# module.net
KiCad netlist of a schematic drawn in EAGLE
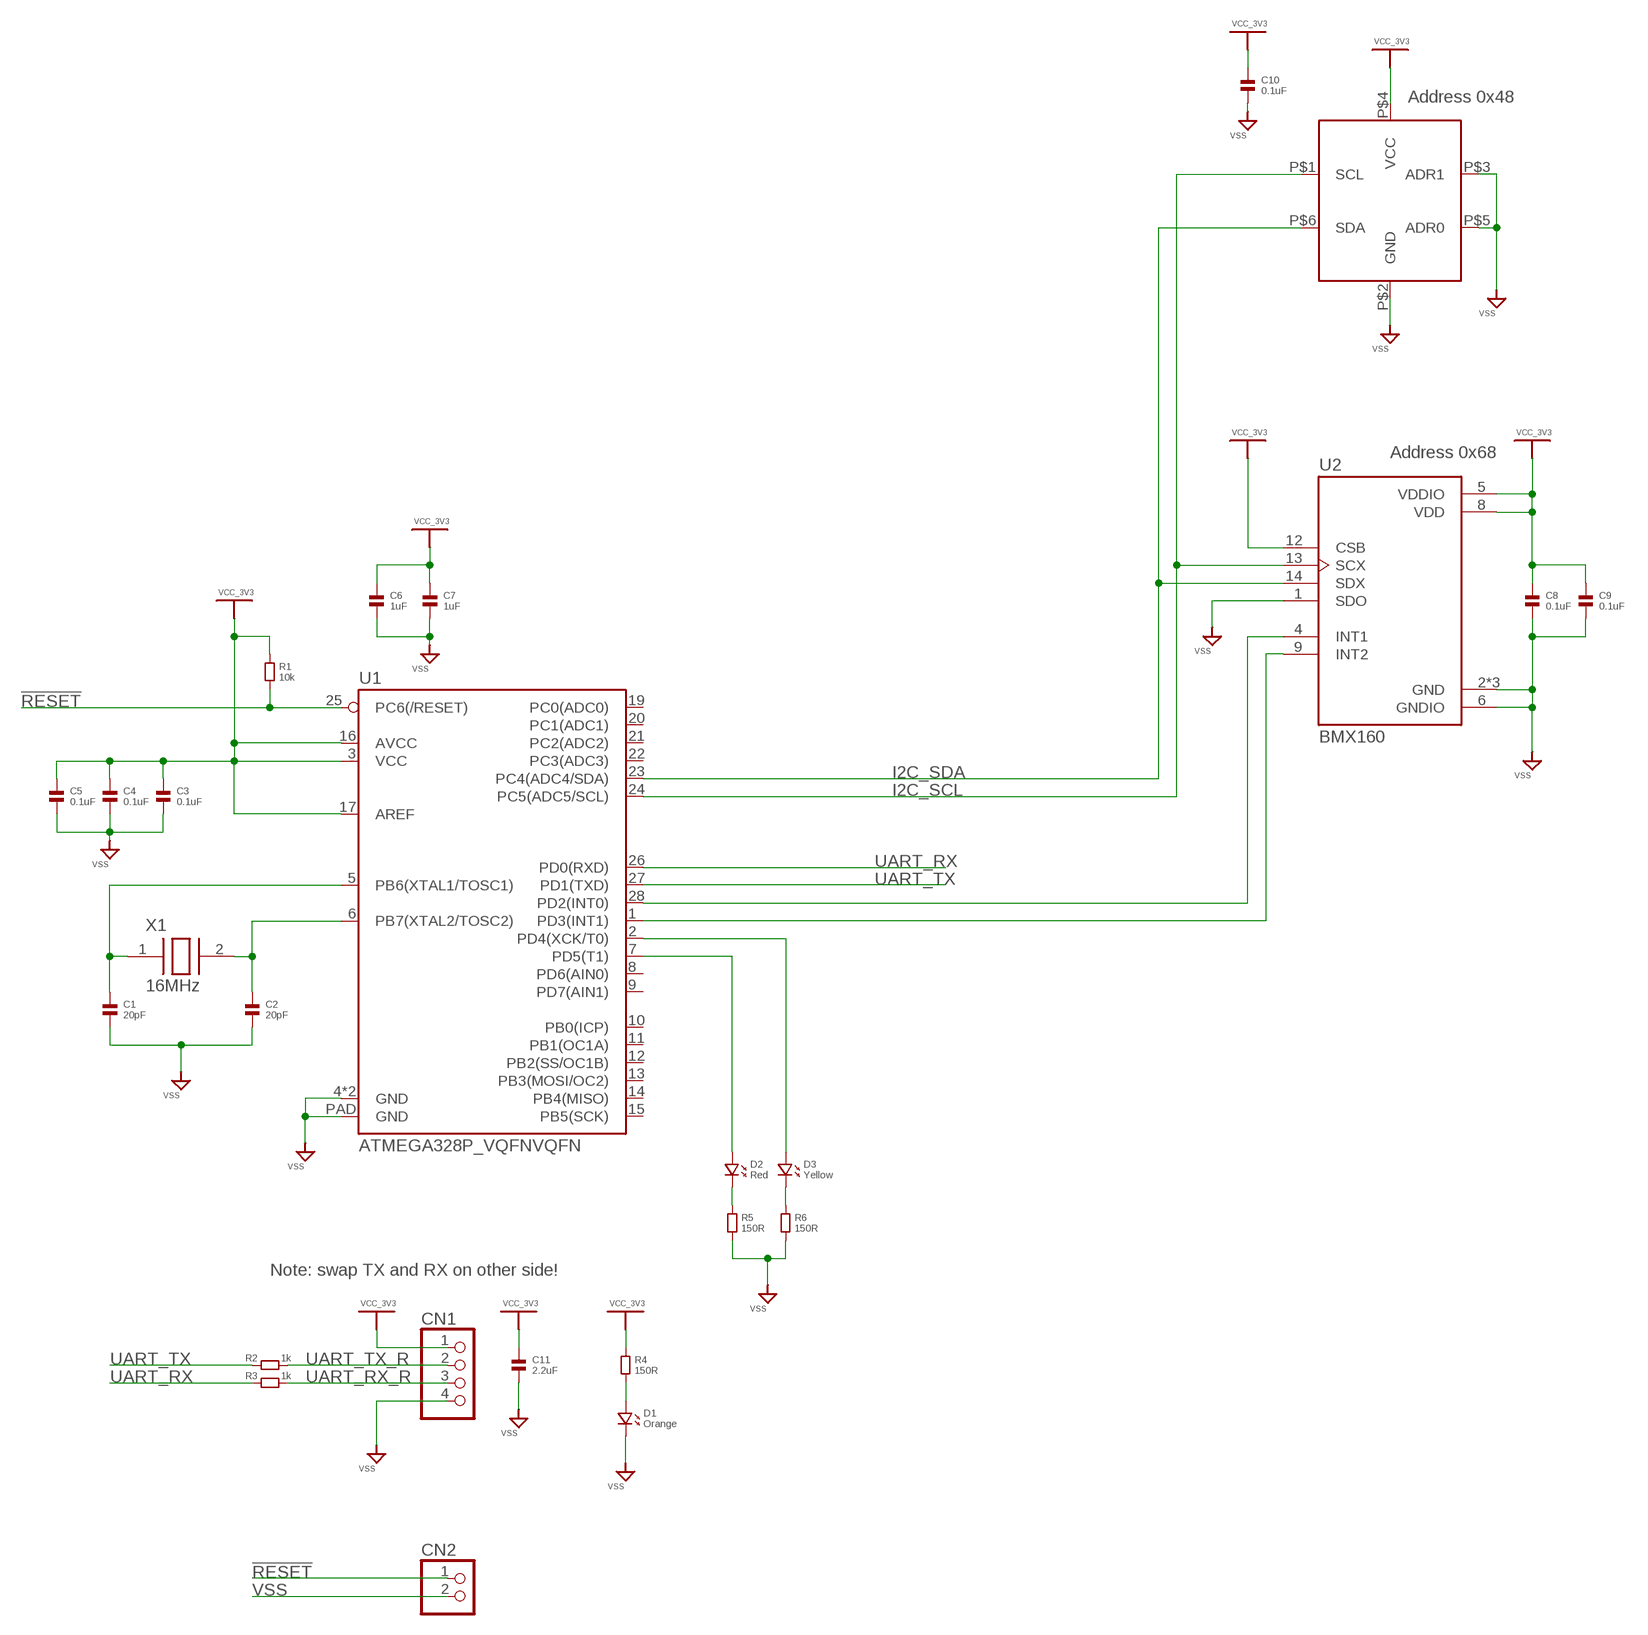
[diagram p0: schematic, sheet 1]

(export (version "E")
  (design (tool "Eeschema 10.0.6"))
  (components
    (comp (ref "C1")
      (value "20pF")
      (footprint "eagle-import:0402")
      (libsource (lib "eagle-import") (part "CAPACITOR.0402"))
    )
    (comp (ref "C2")
      (value "20pF")
      (footprint "eagle-import:0402")
      (libsource (lib "eagle-import") (part "CAPACITOR.0402"))
    )
    (comp (ref "C3")
      (value "0.1uF")
      (footprint "eagle-import:0402")
      (libsource (lib "eagle-import") (part "CAPACITOR.0402"))
    )
    (comp (ref "C4")
      (value "0.1uF")
      (footprint "eagle-import:0402")
      (libsource (lib "eagle-import") (part "CAPACITOR.0402"))
    )
    (comp (ref "C5")
      (value "0.1uF")
      (footprint "eagle-import:0402")
      (libsource (lib "eagle-import") (part "CAPACITOR.0402"))
    )
    (comp (ref "C6")
      (value "1uF")
      (footprint "eagle-import:0603")
      (libsource (lib "eagle-import") (part "CAPACITOR.0603"))
    )
    (comp (ref "C7")
      (value "1uF")
      (footprint "eagle-import:0603")
      (libsource (lib "eagle-import") (part "CAPACITOR.0603"))
    )
    (comp (ref "C8")
      (value "0.1uF")
      (footprint "eagle-import:0402")
      (libsource (lib "eagle-import") (part "CAPACITOR.0402"))
    )
    (comp (ref "C9")
      (value "0.1uF")
      (footprint "eagle-import:0402")
      (libsource (lib "eagle-import") (part "CAPACITOR.0402"))
    )
    (comp (ref "C10")
      (value "0.1uF")
      (footprint "eagle-import:0402")
      (libsource (lib "eagle-import") (part "CAPACITOR.0402"))
    )
    (comp (ref "C11")
      (value "2.2uF")
      (footprint "eagle-import:0603")
      (libsource (lib "eagle-import") (part "CAPACITOR.0603"))
    )
    (comp (ref "CN1")
      (value "JST_4PIN")
      (footprint "eagle-import:JSTPH4")
      (libsource (lib "eagle-import") (part "JST_4PIN"))
    )
    (comp (ref "CN2")
      (value "JST_2PIN")
      (footprint "eagle-import:JSTPH2")
      (libsource (lib "eagle-import") (part "JST_2PIN"))
    )
    (comp (ref "D1")
      (value "Orange")
      (footprint "eagle-import:0603.LED")
      (libsource (lib "eagle-import") (part "LED.0603"))
    )
    (comp (ref "D2")
      (value "Red")
      (footprint "eagle-import:0603.LED")
      (libsource (lib "eagle-import") (part "LED.0603"))
    )
    (comp (ref "D3")
      (value "Yellow")
      (footprint "eagle-import:0603.LED")
      (libsource (lib "eagle-import") (part "LED.0603"))
    )
    (comp (ref "R1")
      (value "10k")
      (footprint "eagle-import:0402")
      (libsource (lib "eagle-import") (part "RESISTOR.0402"))
    )
    (comp (ref "R2")
      (value "1k")
      (footprint "eagle-import:0402")
      (libsource (lib "eagle-import") (part "RESISTOR.0402"))
    )
    (comp (ref "R3")
      (value "1k")
      (footprint "eagle-import:0402")
      (libsource (lib "eagle-import") (part "RESISTOR.0402"))
    )
    (comp (ref "R4")
      (value "150R")
      (footprint "eagle-import:0402")
      (libsource (lib "eagle-import") (part "RESISTOR.0402"))
    )
    (comp (ref "R5")
      (value "150R")
      (footprint "eagle-import:0402")
      (libsource (lib "eagle-import") (part "RESISTOR.0402"))
    )
    (comp (ref "R6")
      (value "150R")
      (footprint "eagle-import:0402")
      (libsource (lib "eagle-import") (part "RESISTOR.0402"))
    )
    (comp (ref "U$1")
      (value "TMP100")
      (footprint "eagle-import:SOT23-6")
      (libsource (lib "eagle-import") (part "TMP100"))
    )
    (comp (ref "U1")
      (value "ATMEGA328P_VQFNVQFN")
      (footprint "eagle-import:VQFN-28")
      (libsource (lib "eagle-import") (part "ATMEGA328P_VQFNVQFN"))
    )
    (comp (ref "U2")
      (value "BMX160")
      (footprint "eagle-import:PQFN50P250X300X100-14N")
      (fields (field (name "MF") "Bosch Sensortec"))
      (libsource (lib "eagle-import") (part "BMX160"))
    )
    (comp (ref "X1")
      (value "16MHz")
      (footprint "eagle-import:ECS_INC-OSCILLATOR-ECS-160-20-23A-TR")
      (libsource (lib "eagle-import") (part "ECS_INC-OSCILLATOR-ECS-160-20-23A-TR"))
    )
  )
  (nets
    (net (code "1") (name "/I2C_SCL") (class "Default")
      (node (ref "U$1") (pin "P$1") (pinfunction "SCL_P$1") (pintype "bidirectional"))
      (node (ref "U1") (pin "24") (pinfunction "PC5(ADC5/SCL)_24") (pintype "bidirectional"))
      (node (ref "U2") (pin "13") (pinfunction "SCX_13") (pintype "input"))
    )
    (net (code "2") (name "/I2C_SDA") (class "Default")
      (node (ref "U$1") (pin "P$6") (pinfunction "SDA_P$6") (pintype "bidirectional"))
      (node (ref "U1") (pin "23") (pinfunction "PC4(ADC4/SDA)_23") (pintype "bidirectional"))
      (node (ref "U2") (pin "14") (pinfunction "SDX_14") (pintype "bidirectional"))
    )
    (net (code "3") (name "/UART_RX") (class "Default")
      (node (ref "R3") (pin "1") (pinfunction "1_1") (pintype "bidirectional"))
      (node (ref "U1") (pin "26") (pinfunction "PD0(RXD)_26") (pintype "bidirectional"))
    )
    (net (code "4") (name "/UART_RX_R") (class "Default")
      (node (ref "CN1") (pin "3") (pinfunction "3_3") (pintype "passive"))
      (node (ref "R3") (pin "2") (pinfunction "2_2") (pintype "bidirectional"))
    )
    (net (code "5") (name "/UART_TX") (class "Default")
      (node (ref "R2") (pin "1") (pinfunction "1_1") (pintype "bidirectional"))
      (node (ref "U1") (pin "27") (pinfunction "PD1(TXD)_27") (pintype "bidirectional"))
    )
    (net (code "6") (name "/UART_TX_R") (class "Default")
      (node (ref "CN1") (pin "2") (pinfunction "2_2") (pintype "passive"))
      (node (ref "R2") (pin "2") (pinfunction "2_2") (pintype "bidirectional"))
    )
    (net (code "7") (name "/~{RESET}") (class "Default")
      (node (ref "CN2") (pin "1") (pinfunction "1_1") (pintype "passive"))
      (node (ref "R1") (pin "2") (pinfunction "2_2") (pintype "bidirectional"))
      (node (ref "U1") (pin "25") (pinfunction "PC6(/RESET)_25") (pintype "bidirectional"))
    )
    (net (code "8") (name "Net-(D1-1)") (class "Default")
      (node (ref "D1") (pin "P$1") (pinfunction "1_P$1") (pintype "bidirectional"))
      (node (ref "R4") (pin "2") (pinfunction "2_2") (pintype "bidirectional"))
    )
    (net (code "9") (name "Net-(D2-1)") (class "Default")
      (node (ref "D2") (pin "P$1") (pinfunction "1_P$1") (pintype "bidirectional"))
      (node (ref "U1") (pin "7") (pinfunction "PD5(T1)_7") (pintype "bidirectional"))
    )
    (net (code "10") (name "Net-(D2-2)") (class "Default")
      (node (ref "D2") (pin "P$2") (pinfunction "2_P$2") (pintype "bidirectional"))
      (node (ref "R5") (pin "1") (pinfunction "1_1") (pintype "bidirectional"))
    )
    (net (code "11") (name "Net-(D3-1)") (class "Default")
      (node (ref "D3") (pin "P$1") (pinfunction "1_P$1") (pintype "bidirectional"))
      (node (ref "U1") (pin "2") (pinfunction "PD4(XCK/T0)_2") (pintype "bidirectional"))
    )
    (net (code "12") (name "Net-(D3-2)") (class "Default")
      (node (ref "D3") (pin "P$2") (pinfunction "2_P$2") (pintype "bidirectional"))
      (node (ref "R6") (pin "1") (pinfunction "1_1") (pintype "bidirectional"))
    )
    (net (code "13") (name "Net-(U1-PB6(XTAL1{slash}TOSC1))") (class "Default")
      (node (ref "C1") (pin "1") (pinfunction "1_1") (pintype "bidirectional"))
      (node (ref "U1") (pin "5") (pinfunction "PB6(XTAL1/TOSC1)_5") (pintype "bidirectional"))
      (node (ref "X1") (pin "1") (pinfunction "XI_1") (pintype "bidirectional"))
    )
    (net (code "14") (name "Net-(U1-PB7(XTAL2{slash}TOSC2))") (class "Default")
      (node (ref "C2") (pin "1") (pinfunction "1_1") (pintype "bidirectional"))
      (node (ref "U1") (pin "6") (pinfunction "PB7(XTAL2/TOSC2)_6") (pintype "bidirectional"))
      (node (ref "X1") (pin "2") (pinfunction "XO_2") (pintype "bidirectional"))
    )
    (net (code "15") (name "Net-(U1-PD2(INT0))") (class "Default")
      (node (ref "U1") (pin "28") (pinfunction "PD2(INT0)_28") (pintype "bidirectional"))
      (node (ref "U2") (pin "4") (pinfunction "INT1_4") (pintype "bidirectional"))
    )
    (net (code "16") (name "Net-(U1-PD3(INT1))") (class "Default")
      (node (ref "U1") (pin "1") (pinfunction "PD3(INT1)_1") (pintype "bidirectional"))
      (node (ref "U2") (pin "9") (pinfunction "INT2_9") (pintype "bidirectional"))
    )
    (net (code "17") (name "VCC_3V3") (class "Default")
      (node (ref "C10") (pin "1") (pinfunction "1_1") (pintype "bidirectional"))
      (node (ref "C11") (pin "1") (pinfunction "1_1") (pintype "bidirectional"))
      (node (ref "C3") (pin "1") (pinfunction "1_1") (pintype "bidirectional"))
      (node (ref "C4") (pin "1") (pinfunction "1_1") (pintype "bidirectional"))
      (node (ref "C5") (pin "1") (pinfunction "1_1") (pintype "bidirectional"))
      (node (ref "C6") (pin "1") (pinfunction "1_1") (pintype "bidirectional"))
      (node (ref "C7") (pin "1") (pinfunction "1_1") (pintype "bidirectional"))
      (node (ref "C8") (pin "1") (pinfunction "1_1") (pintype "bidirectional"))
      (node (ref "C9") (pin "1") (pinfunction "1_1") (pintype "bidirectional"))
      (node (ref "CN1") (pin "1") (pinfunction "1_1") (pintype "passive"))
      (node (ref "R1") (pin "1") (pinfunction "1_1") (pintype "bidirectional"))
      (node (ref "R4") (pin "1") (pinfunction "1_1") (pintype "bidirectional"))
      (node (ref "U$1") (pin "P$4") (pinfunction "VCC_P$4") (pintype "power_in"))
      (node (ref "U1") (pin "16") (pinfunction "AVCC_16") (pintype "bidirectional"))
      (node (ref "U1") (pin "17") (pinfunction "AREF_17") (pintype "bidirectional"))
      (node (ref "U1") (pin "3") (pinfunction "VCC_3") (pintype "bidirectional"))
      (node (ref "U2") (pin "12") (pinfunction "CSB_12") (pintype "input"))
      (node (ref "U2") (pin "5") (pinfunction "VDDIO_5") (pintype "power_in"))
      (node (ref "U2") (pin "8") (pinfunction "VDD_8") (pintype "power_in"))
    )
    (net (code "18") (name "VSS") (class "Default")
      (node (ref "C1") (pin "2") (pinfunction "2_2") (pintype "bidirectional"))
      (node (ref "C10") (pin "2") (pinfunction "2_2") (pintype "bidirectional"))
      (node (ref "C11") (pin "2") (pinfunction "2_2") (pintype "bidirectional"))
      (node (ref "C2") (pin "2") (pinfunction "2_2") (pintype "bidirectional"))
      (node (ref "C3") (pin "2") (pinfunction "2_2") (pintype "bidirectional"))
      (node (ref "C4") (pin "2") (pinfunction "2_2") (pintype "bidirectional"))
      (node (ref "C5") (pin "2") (pinfunction "2_2") (pintype "bidirectional"))
      (node (ref "C6") (pin "2") (pinfunction "2_2") (pintype "bidirectional"))
      (node (ref "C7") (pin "2") (pinfunction "2_2") (pintype "bidirectional"))
      (node (ref "C8") (pin "2") (pinfunction "2_2") (pintype "bidirectional"))
      (node (ref "C9") (pin "2") (pinfunction "2_2") (pintype "bidirectional"))
      (node (ref "CN1") (pin "4") (pinfunction "4_4") (pintype "passive"))
      (node (ref "CN2") (pin "2") (pinfunction "2_2") (pintype "passive"))
      (node (ref "D1") (pin "P$2") (pinfunction "2_P$2") (pintype "bidirectional"))
      (node (ref "R5") (pin "2") (pinfunction "2_2") (pintype "bidirectional"))
      (node (ref "R6") (pin "2") (pinfunction "2_2") (pintype "bidirectional"))
      (node (ref "U$1") (pin "P$2") (pinfunction "GND_P$2") (pintype "power_in"))
      (node (ref "U$1") (pin "P$3") (pinfunction "ADR1_P$3") (pintype "bidirectional"))
      (node (ref "U$1") (pin "P$5") (pinfunction "ADR0_P$5") (pintype "bidirectional"))
      (node (ref "U1") (pin "18") (pinfunction "GND_18") (pintype "bidirectional"))
      (node (ref "U1") (pin "4") (pinfunction "GND_4") (pintype "bidirectional"))
      (node (ref "U1") (pin "PAD") (pinfunction "GND_PAD") (pintype "bidirectional"))
      (node (ref "U2") (pin "1") (pinfunction "SDO_1") (pintype "bidirectional"))
      (node (ref "U2") (pin "2") (pinfunction "GND_2") (pintype "power_in"))
      (node (ref "U2") (pin "3") (pinfunction "GND_3") (pintype "power_in"))
      (node (ref "U2") (pin "6") (pinfunction "GNDIO_6") (pintype "power_in"))
      (node (ref "U2") (pin "7") (pinfunction "GND_7") (pintype "power_in"))
    )
    (net (code "19") (name "unconnected-(U1-PB0(ICP)-Pad10)") (class "Default")
      (node (ref "U1") (pin "10") (pinfunction "PB0(ICP)_10") (pintype "bidirectional"))
    )
    (net (code "20") (name "unconnected-(U1-PB1(OC1A)-Pad11)") (class "Default")
      (node (ref "U1") (pin "11") (pinfunction "PB1(OC1A)_11") (pintype "bidirectional"))
    )
    (net (code "21") (name "unconnected-(U1-PB2(SS{slash}OC1B)-Pad12)") (class "Default")
      (node (ref "U1") (pin "12") (pinfunction "PB2(SS/OC1B)_12") (pintype "bidirectional"))
    )
    (net (code "22") (name "unconnected-(U1-PB3(MOSI{slash}OC2)-Pad13)") (class "Default")
      (node (ref "U1") (pin "13") (pinfunction "PB3(MOSI/OC2)_13") (pintype "bidirectional"))
    )
    (net (code "23") (name "unconnected-(U1-PB4(MISO)-Pad14)") (class "Default")
      (node (ref "U1") (pin "14") (pinfunction "PB4(MISO)_14") (pintype "bidirectional"))
    )
    (net (code "24") (name "unconnected-(U1-PB5(SCK)-Pad15)") (class "Default")
      (node (ref "U1") (pin "15") (pinfunction "PB5(SCK)_15") (pintype "bidirectional"))
    )
    (net (code "25") (name "unconnected-(U1-PC0(ADC0)-Pad19)") (class "Default")
      (node (ref "U1") (pin "19") (pinfunction "PC0(ADC0)_19") (pintype "bidirectional"))
    )
    (net (code "26") (name "unconnected-(U1-PC1(ADC1)-Pad20)") (class "Default")
      (node (ref "U1") (pin "20") (pinfunction "PC1(ADC1)_20") (pintype "bidirectional"))
    )
    (net (code "27") (name "unconnected-(U1-PC2(ADC2)-Pad21)") (class "Default")
      (node (ref "U1") (pin "21") (pinfunction "PC2(ADC2)_21") (pintype "bidirectional"))
    )
    (net (code "28") (name "unconnected-(U1-PC3(ADC3)-Pad22)") (class "Default")
      (node (ref "U1") (pin "22") (pinfunction "PC3(ADC3)_22") (pintype "bidirectional"))
    )
    (net (code "29") (name "unconnected-(U1-PD6(AIN0)-Pad8)") (class "Default")
      (node (ref "U1") (pin "8") (pinfunction "PD6(AIN0)_8") (pintype "bidirectional"))
    )
    (net (code "30") (name "unconnected-(U1-PD7(AIN1)-Pad9)") (class "Default")
      (node (ref "U1") (pin "9") (pinfunction "PD7(AIN1)_9") (pintype "bidirectional"))
    )
  )
)
